# PWR_LD1117S33.net
KiCad netlist of a schematic drawn in Altium Designer
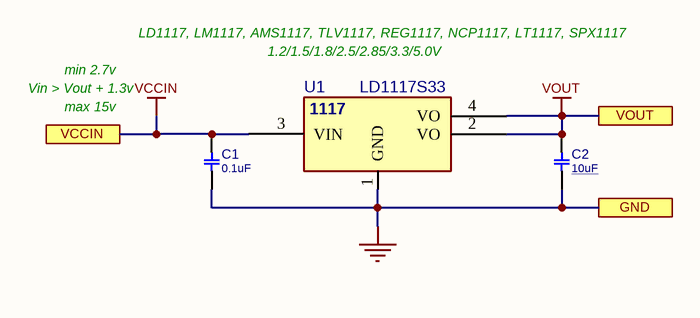
[diagram p0: PWR_LD1117S33.SchDoc]

(export (version "E")
  (design (tool "Eeschema 10.0.6"))
  (components
    (comp (ref "C1")
      (value "0.1uF")
      (footprint "C0402")
      (description "CAP, MLCC")
      (libsource (lib "mlcc_smd_passive") (part "CAP_SMD_MLCC_100n50T"))
    )
    (comp (ref "C2")
      (value "10uF")
      (footprint "C0402")
      (description "CAP, MLCC")
      (libsource (lib "passive_smd") (part "CAP_SMD_MLCC"))
    )
    (comp (ref "U1")
      (value "LD1117S33")
      (footprint "SOT223_4")
      (description "REG, Linear, LDO1V, 0.8A, SOT-223")
      (fields
        (field (name "MANF_P#") "LD1117, LM1117, AMS1117, TLV1117, REG1117, NCP1117, LT1117, SPX1117")
        (field (name "MANF") "TI, ON, ST")
      )
      (libsource (lib "pwr_reg_linear_1117") (part "VREG_1117_SOT223"))
    )
  )
  (nets
    (net (code "1") (name "GND") (class "Default")
      (node (ref "C1") (pin "2") (pinfunction "2_2") (pintype "passive"))
      (node (ref "C2") (pin "2") (pinfunction "2_2") (pintype "passive"))
      (node (ref "U1") (pin "1") (pinfunction "GND_1") (pintype "passive"))
    )
    (net (code "2") (name "VCCIN") (class "Default")
      (node (ref "C1") (pin "1") (pinfunction "1_1") (pintype "passive"))
      (node (ref "U1") (pin "3") (pinfunction "VIN_3") (pintype "passive"))
    )
    (net (code "3") (name "VOUT") (class "Default")
      (node (ref "C2") (pin "1") (pinfunction "1_1") (pintype "passive"))
      (node (ref "U1") (pin "2") (pinfunction "VO_2") (pintype "passive"))
      (node (ref "U1") (pin "4") (pinfunction "VO_4") (pintype "passive"))
    )
  )
)
